# sender.net
KiCad netlist of a schematic drawn in Altium Designer
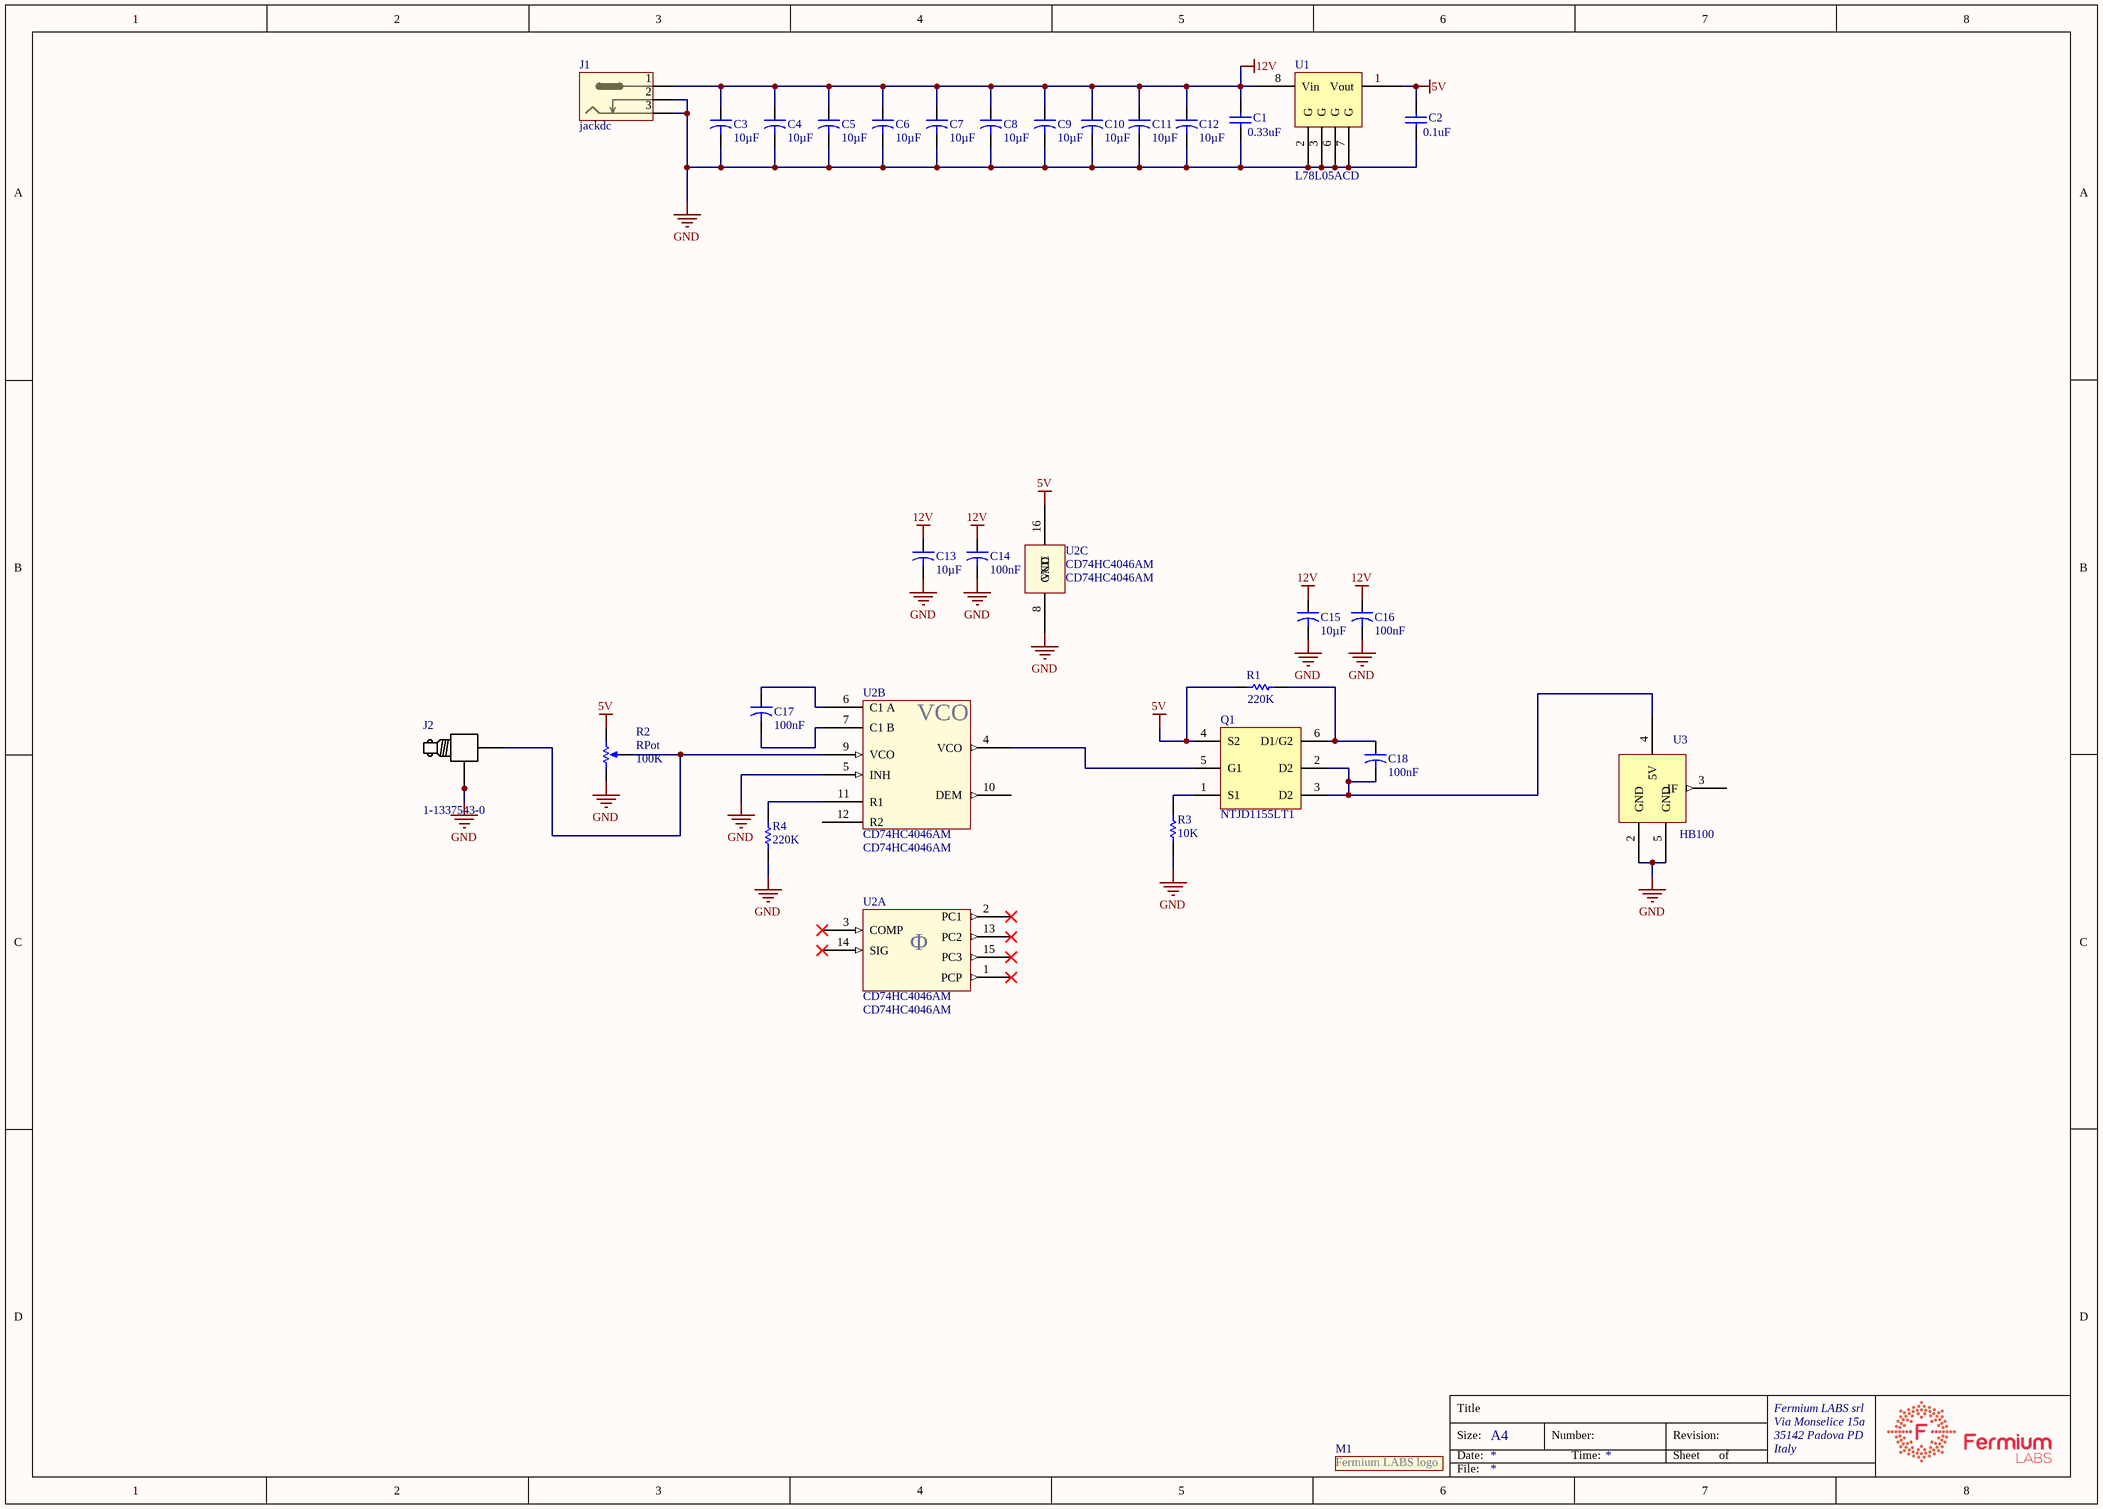
[diagram p0: sender.SchDoc]

(export (version "E")
  (design (tool "Eeschema 10.0.6"))
  (components
    (comp (ref "C1")
      (value "0.33uF")
      (footprint "RAD-0.3")
      (description "Capacitor")
      (fields (field (name "PUBLISHER") "Altium Limited"))
      (libsource (lib "Miscellaneous Devices") (part "Cap"))
    )
    (comp (ref "C2")
      (value "0.1uF")
      (footprint "RAD-0.3")
      (description "Capacitor")
      (fields (field (name "PUBLISHER") "Altium Limited"))
      (libsource (lib "Miscellaneous Devices") (part "Cap"))
    )
    (comp (ref "C3")
      (value "~")
      (footprint "Passives:CAP 1206/3216")
      (description "Capacitor")
      (fields
        (field (name "MANUFACTURER") "SAMSUNG")
        (field (name "MANUFACTURER PART NUMBER") "CL31A106KAHNNNE")
        (field (name "CAPACITANCE") "10µF")
        (field (name "PUBLISHER") "Altium Limited")
      )
      (libsource (lib "Miscellaneous Devices") (part "Cap2"))
    )
    (comp (ref "C4")
      (value "~")
      (footprint "Passives:CAP 1206/3216")
      (description "Capacitor")
      (fields
        (field (name "MANUFACTURER") "SAMSUNG")
        (field (name "MANUFACTURER PART NUMBER") "CL31A106KAHNNNE")
        (field (name "CAPACITANCE") "10µF")
        (field (name "PUBLISHER") "Altium Limited")
      )
      (libsource (lib "Miscellaneous Devices") (part "Cap2"))
    )
    (comp (ref "C5")
      (value "~")
      (footprint "Passives:CAP 1206/3216")
      (description "Capacitor")
      (fields
        (field (name "MANUFACTURER") "SAMSUNG")
        (field (name "MANUFACTURER PART NUMBER") "CL31A106KAHNNNE")
        (field (name "CAPACITANCE") "10µF")
        (field (name "PUBLISHER") "Altium Limited")
      )
      (libsource (lib "Miscellaneous Devices") (part "Cap2"))
    )
    (comp (ref "C6")
      (value "~")
      (footprint "Passives:CAP 1206/3216")
      (description "Capacitor")
      (fields
        (field (name "MANUFACTURER") "SAMSUNG")
        (field (name "MANUFACTURER PART NUMBER") "CL31A106KAHNNNE")
        (field (name "CAPACITANCE") "10µF")
        (field (name "PUBLISHER") "Altium Limited")
      )
      (libsource (lib "Miscellaneous Devices") (part "Cap2"))
    )
    (comp (ref "C7")
      (value "~")
      (footprint "Passives:CAP 1206/3216")
      (description "Capacitor")
      (fields
        (field (name "MANUFACTURER") "SAMSUNG")
        (field (name "MANUFACTURER PART NUMBER") "CL31A106KAHNNNE")
        (field (name "CAPACITANCE") "10µF")
        (field (name "PUBLISHER") "Altium Limited")
      )
      (libsource (lib "Miscellaneous Devices") (part "Cap2"))
    )
    (comp (ref "C8")
      (value "~")
      (footprint "Passives:CAP 1206/3216")
      (description "Capacitor")
      (fields
        (field (name "MANUFACTURER") "SAMSUNG")
        (field (name "MANUFACTURER PART NUMBER") "CL31A106KAHNNNE")
        (field (name "CAPACITANCE") "10µF")
        (field (name "PUBLISHER") "Altium Limited")
      )
      (libsource (lib "Miscellaneous Devices") (part "Cap2"))
    )
    (comp (ref "C9")
      (value "~")
      (footprint "Passives:CAP 1206/3216")
      (description "Capacitor")
      (fields
        (field (name "MANUFACTURER") "SAMSUNG")
        (field (name "MANUFACTURER PART NUMBER") "CL31A106KAHNNNE")
        (field (name "CAPACITANCE") "10µF")
        (field (name "PUBLISHER") "Altium Limited")
      )
      (libsource (lib "Miscellaneous Devices") (part "Cap2"))
    )
    (comp (ref "C10")
      (value "~")
      (footprint "Passives:CAP 1206/3216")
      (description "Capacitor")
      (fields
        (field (name "MANUFACTURER") "SAMSUNG")
        (field (name "MANUFACTURER PART NUMBER") "CL31A106KAHNNNE")
        (field (name "CAPACITANCE") "10µF")
        (field (name "PUBLISHER") "Altium Limited")
      )
      (libsource (lib "Miscellaneous Devices") (part "Cap2"))
    )
    (comp (ref "C11")
      (value "~")
      (footprint "Passives:CAP 1206/3216")
      (description "Capacitor")
      (fields
        (field (name "MANUFACTURER") "SAMSUNG")
        (field (name "MANUFACTURER PART NUMBER") "CL31A106KAHNNNE")
        (field (name "CAPACITANCE") "10µF")
        (field (name "PUBLISHER") "Altium Limited")
      )
      (libsource (lib "Miscellaneous Devices") (part "Cap2"))
    )
    (comp (ref "C12")
      (value "~")
      (footprint "Passives:CAP 1206/3216")
      (description "Capacitor")
      (fields
        (field (name "MANUFACTURER") "SAMSUNG")
        (field (name "MANUFACTURER PART NUMBER") "CL31A106KAHNNNE")
        (field (name "CAPACITANCE") "10µF")
        (field (name "PUBLISHER") "Altium Limited")
      )
      (libsource (lib "Miscellaneous Devices") (part "Cap2"))
    )
    (comp (ref "C13")
      (value "~")
      (footprint "Passives:CAP 1206/3216")
      (description "Capacitor")
      (fields
        (field (name "MANUFACTURER") "SAMSUNG")
        (field (name "MANUFACTURER PART NUMBER") "CL31A106KAHNNNE")
        (field (name "CAPACITANCE") "10µF")
        (field (name "PUBLISHER") "Altium Limited")
      )
      (libsource (lib "Miscellaneous Devices") (part "Cap2"))
    )
    (comp (ref "C14")
      (value "~")
      (footprint "Passives:CAP 0805/2012")
      (description "Capacitor")
      (fields
        (field (name "CAPACITANCE") "100nF")
        (field (name "MANUFACTURER") "YAGEO")
        (field (name "MANUFACTURER PART NUMBER") "CC0805JRX7R9BB104")
      )
      (libsource (lib "Miscellaneous Devices") (part "Cap2"))
    )
    (comp (ref "C15")
      (value "~")
      (footprint "Passives:CAP 1206/3216")
      (description "Capacitor")
      (fields
        (field (name "MANUFACTURER") "SAMSUNG")
        (field (name "MANUFACTURER PART NUMBER") "CL31A106KAHNNNE")
        (field (name "CAPACITANCE") "10µF")
        (field (name "PUBLISHER") "Altium Limited")
      )
      (libsource (lib "Miscellaneous Devices") (part "Cap2"))
    )
    (comp (ref "C16")
      (value "~")
      (footprint "Passives:CAP 0805/2012")
      (description "Capacitor")
      (fields
        (field (name "CAPACITANCE") "100nF")
        (field (name "MANUFACTURER") "YAGEO")
        (field (name "MANUFACTURER PART NUMBER") "CC0805JRX7R9BB104")
      )
      (libsource (lib "Miscellaneous Devices") (part "Cap2"))
    )
    (comp (ref "C17")
      (value "~")
      (footprint "Passives:CAP 0805/2012")
      (description "Capacitor")
      (fields
        (field (name "CAPACITANCE") "100nF")
        (field (name "MANUFACTURER") "YAGEO")
        (field (name "MANUFACTURER PART NUMBER") "CC0805JRX7R9BB104")
      )
      (libsource (lib "Miscellaneous Devices") (part "Cap2"))
    )
    (comp (ref "C18")
      (value "~")
      (footprint "Passives:CAP 0805/2012")
      (description "Capacitor")
      (fields
        (field (name "CAPACITANCE") "100nF")
        (field (name "MANUFACTURER") "YAGEO")
        (field (name "MANUFACTURER PART NUMBER") "CC0805JRX7R9BB104")
      )
      (libsource (lib "Miscellaneous Devices") (part "Cap2"))
    )
    (comp (ref "J1")
      (value "jackdc")
      (footprint "custom_components:dc-jack")
      (libsource (lib "custom_components") (part "jackdc"))
    )
    (comp (ref "J2")
      (value "~")
      (footprint "BNC-RA")
      (description "connector bnc")
      (fields
        (field (name "SUPPLIER PART NUMBER 1") "1-1337543-0")
        (field (name "MANUFACTURER") "TE CONNECTIVITY")
        (field (name "MANUFACTURER PART NUMBER") "1-1337543-0")
      )
      (libsource (lib "TH Connectors") (part "BNC-PCB-RA"))
    )
    (comp (ref "M1")
      (value "fermiumlabs-logo")
      (footprint "frm-small")
      (libsource (lib "custom_components") (part "fermiumlabs-logo"))
    )
    (comp (ref "Q1")
      (value "NTJD1155LT1")
      (footprint "ONSC-SC70-6-419B-02_W_V")
      (fields (field (name "MANUFACTURER") "On Semiconductor"))
      (libsource (lib "ON Semi MOSFETs") (part "NTJD1155LT1"))
    )
    (comp (ref "R1")
      (value "220K")
      (footprint "RES 0805/2012")
      (description "Resistor")
      (fields
        (field (name "MANUFACTURER") "Royal Electronic Factory")
        (field (name "MANUFACTURER PART NUMBER") "0805S8J0224T5E")
      )
      (libsource (lib "Miscellaneous Devices") (part "Res1"))
    )
    (comp (ref "R2")
      (value "RPot")
      (footprint "VR5")
      (description "Potentiometer")
      (fields (field (name "ALTIUM_VALUE") "100K"))
      (libsource (lib "Miscellaneous Devices") (part "RPot"))
    )
    (comp (ref "R3")
      (value "10K")
      (footprint "AXIAL-0.3")
      (description "Resistor")
      (fields (field (name "Comment") "Res1") (field (name "PUBLISHER") "Altium Limited"))
      (libsource (lib "Miscellaneous Devices") (part "Res1"))
    )
    (comp (ref "R4")
      (value "220K")
      (footprint "RES 0805/2012")
      (description "Resistor")
      (fields
        (field (name "MANUFACTURER") "Royal Electronic Factory")
        (field (name "MANUFACTURER PART NUMBER") "0805S8J0224T5E")
      )
      (libsource (lib "Miscellaneous Devices") (part "Res1"))
    )
    (comp (ref "U1")
      (value "L78L05ACD")
      (footprint "ST SOIC-8N")
      (fields (field (name "SUPPLIER PART NUMBER 1") "L78L05ACD"))
      (libsource (lib "custom_components_ltk_mw") (part "L78L05ACD"))
    )
    (comp (ref "U2")
      (value "CD74HC4046AM")
      (footprint "SO16")
      (fields (field (name "SUPPLIER PART NUMBER 1") "CD74HC4046AM"))
      (libsource (lib "custom_components_ltk_mw") (part "CD74HC4046AM"))
    )
    (comp (ref "U3")
      (value "HB100")
      (footprint "HB100")
      (fields
        (field (name "MANUFACTURER") "China unspecified")
        (field (name "SUPPLIER PART NUMBER 1") "HB100")
      )
      (libsource (lib "custom_components_ltk_mw") (part "HB100"))
    )
  )
  (nets
    (net (code "1") (name "5V") (class "Default")
      (node (ref "C2") (pin "2") (pinfunction "2_2") (pintype "passive"))
      (node (ref "Q1") (pin "4") (pinfunction "S2_4") (pintype "passive"))
      (node (ref "R1") (pin "1") (pinfunction "1_1") (pintype "passive"))
      (node (ref "R2") (pin "2") (pinfunction "BOT_2") (pintype "passive"))
      (node (ref "U1") (pin "1") (pinfunction "Vout_1") (pintype "power_in"))
      (node (ref "U2") (pin "16") (pinfunction "VCC_16") (pintype "power_in"))
    )
    (net (code "2") (name "12V") (class "Default")
      (node (ref "C1") (pin "2") (pinfunction "2_2") (pintype "passive"))
      (node (ref "C10") (pin "1") (pinfunction "1_1") (pintype "passive"))
      (node (ref "C11") (pin "1") (pinfunction "1_1") (pintype "passive"))
      (node (ref "C12") (pin "1") (pinfunction "1_1") (pintype "passive"))
      (node (ref "C13") (pin "1") (pinfunction "1_1") (pintype "passive"))
      (node (ref "C14") (pin "1") (pinfunction "1_1") (pintype "passive"))
      (node (ref "C15") (pin "1") (pinfunction "1_1") (pintype "passive"))
      (node (ref "C16") (pin "1") (pinfunction "1_1") (pintype "passive"))
      (node (ref "C3") (pin "1") (pinfunction "1_1") (pintype "passive"))
      (node (ref "C4") (pin "1") (pinfunction "1_1") (pintype "passive"))
      (node (ref "C5") (pin "1") (pinfunction "1_1") (pintype "passive"))
      (node (ref "C6") (pin "1") (pinfunction "1_1") (pintype "passive"))
      (node (ref "C7") (pin "1") (pinfunction "1_1") (pintype "passive"))
      (node (ref "C8") (pin "1") (pinfunction "1_1") (pintype "passive"))
      (node (ref "C9") (pin "1") (pinfunction "1_1") (pintype "passive"))
      (node (ref "J1") (pin "1") (pinfunction "1_1") (pintype "passive"))
      (node (ref "U1") (pin "8") (pinfunction "Vin_8") (pintype "power_in"))
    )
    (net (code "3") (name "GND") (class "Default")
      (node (ref "C1") (pin "1") (pinfunction "1_1") (pintype "passive"))
      (node (ref "C10") (pin "2") (pinfunction "2_2") (pintype "passive"))
      (node (ref "C11") (pin "2") (pinfunction "2_2") (pintype "passive"))
      (node (ref "C12") (pin "2") (pinfunction "2_2") (pintype "passive"))
      (node (ref "C13") (pin "2") (pinfunction "2_2") (pintype "passive"))
      (node (ref "C14") (pin "2") (pinfunction "2_2") (pintype "passive"))
      (node (ref "C15") (pin "2") (pinfunction "2_2") (pintype "passive"))
      (node (ref "C16") (pin "2") (pinfunction "2_2") (pintype "passive"))
      (node (ref "C2") (pin "1") (pinfunction "1_1") (pintype "passive"))
      (node (ref "C3") (pin "2") (pinfunction "2_2") (pintype "passive"))
      (node (ref "C4") (pin "2") (pinfunction "2_2") (pintype "passive"))
      (node (ref "C5") (pin "2") (pinfunction "2_2") (pintype "passive"))
      (node (ref "C6") (pin "2") (pinfunction "2_2") (pintype "passive"))
      (node (ref "C7") (pin "2") (pinfunction "2_2") (pintype "passive"))
      (node (ref "C8") (pin "2") (pinfunction "2_2") (pintype "passive"))
      (node (ref "C9") (pin "2") (pinfunction "2_2") (pintype "passive"))
      (node (ref "J1") (pin "2") (pinfunction "2_2") (pintype "passive"))
      (node (ref "J1") (pin "3") (pinfunction "3_3") (pintype "passive"))
      (node (ref "J2") (pin "2") (pinfunction "gnd_2") (pintype "passive"))
      (node (ref "J2") (pin "A") (pinfunction "A_A") (pintype "passive"))
      (node (ref "J2") (pin "B") (pinfunction "B_B") (pintype "passive"))
      (node (ref "R2") (pin "1") (pinfunction "TOP_1") (pintype "passive"))
      (node (ref "R3") (pin "2") (pinfunction "2_2") (pintype "passive"))
      (node (ref "R4") (pin "1") (pinfunction "1_1") (pintype "passive"))
      (node (ref "U1") (pin "2") (pinfunction "G_2") (pintype "power_in"))
      (node (ref "U1") (pin "3") (pinfunction "G_3") (pintype "power_in"))
      (node (ref "U1") (pin "6") (pinfunction "G_6") (pintype "power_in"))
      (node (ref "U1") (pin "7") (pinfunction "G_7") (pintype "power_in"))
      (node (ref "U2") (pin "5") (pinfunction "INH_5") (pintype "input"))
      (node (ref "U2") (pin "8") (pinfunction "GND_8") (pintype "power_in"))
      (node (ref "U3") (pin "2") (pinfunction "GND_2") (pintype "power_in"))
      (node (ref "U3") (pin "5") (pinfunction "GND_5") (pintype "power_in"))
    )
    (net (code "4") (name "Net-(Q1-D1{slash}G2)") (class "Default")
      (node (ref "C18") (pin "1") (pinfunction "1_1") (pintype "passive"))
      (node (ref "Q1") (pin "6") (pinfunction "D1/G2_6") (pintype "passive"))
      (node (ref "R1") (pin "2") (pinfunction "2_2") (pintype "passive"))
    )
    (net (code "5") (name "Net-(Q1-G1)") (class "Default")
      (node (ref "Q1") (pin "5") (pinfunction "G1_5") (pintype "passive"))
      (node (ref "U2") (pin "4") (pinfunction "VCO_4") (pintype "output"))
    )
    (net (code "6") (name "Net-(Q1-S1)") (class "Default")
      (node (ref "Q1") (pin "1") (pinfunction "S1_1") (pintype "passive"))
      (node (ref "R3") (pin "1") (pinfunction "1_1") (pintype "passive"))
    )
    (net (code "7") (name "Net-(R2-TAP)") (class "Default")
      (node (ref "J2") (pin "1") (pinfunction "1_1") (pintype "passive"))
      (node (ref "R2") (pin "3") (pinfunction "TAP_3") (pintype "passive"))
      (node (ref "U2") (pin "9") (pinfunction "VCO_9") (pintype "input"))
    )
    (net (code "8") (name "Net-(U2B-C1_A)") (class "Default")
      (node (ref "C17") (pin "1") (pinfunction "1_1") (pintype "passive"))
      (node (ref "U2") (pin "6") (pinfunction "C1_A_6") (pintype "passive"))
    )
    (net (code "9") (name "Net-(U2B-C1_B)") (class "Default")
      (node (ref "C17") (pin "2") (pinfunction "2_2") (pintype "passive"))
      (node (ref "U2") (pin "7") (pinfunction "C1_B_7") (pintype "passive"))
    )
    (net (code "10") (name "Net-(U2B-R1)") (class "Default")
      (node (ref "R4") (pin "2") (pinfunction "2_2") (pintype "passive"))
      (node (ref "U2") (pin "11") (pinfunction "R1_11") (pintype "passive"))
    )
    (net (code "11") (name "Net-(U3-5V)") (class "Default")
      (node (ref "C18") (pin "2") (pinfunction "2_2") (pintype "passive"))
      (node (ref "Q1") (pin "2") (pinfunction "D2_2") (pintype "passive"))
      (node (ref "Q1") (pin "3") (pinfunction "D2_3") (pintype "passive"))
      (node (ref "U3") (pin "4") (pinfunction "5V_4") (pintype "power_in"))
    )
    (net (code "12") (name "unconnected-(U2A-COMP-Pad3)") (class "Default")
      (node (ref "U2") (pin "3") (pinfunction "COMP_3") (pintype "input+no_connect"))
    )
    (net (code "13") (name "unconnected-(U2A-PC1-Pad2)") (class "Default")
      (node (ref "U2") (pin "2") (pinfunction "PC1_2") (pintype "output+no_connect"))
    )
    (net (code "14") (name "unconnected-(U2A-PC2-Pad13)") (class "Default")
      (node (ref "U2") (pin "13") (pinfunction "PC2_13") (pintype "output+no_connect"))
    )
    (net (code "15") (name "unconnected-(U2A-PC3-Pad15)") (class "Default")
      (node (ref "U2") (pin "15") (pinfunction "PC3_15") (pintype "output+no_connect"))
    )
    (net (code "16") (name "unconnected-(U2A-PCP-Pad1)") (class "Default")
      (node (ref "U2") (pin "1") (pinfunction "PCP_1") (pintype "output+no_connect"))
    )
    (net (code "17") (name "unconnected-(U2A-SIG-Pad14)") (class "Default")
      (node (ref "U2") (pin "14") (pinfunction "SIG_14") (pintype "input+no_connect"))
    )
    (net (code "18") (name "unconnected-(U2B-DEM-Pad10)") (class "Default")
      (node (ref "U2") (pin "10") (pinfunction "DEM_10") (pintype "output"))
    )
    (net (code "19") (name "unconnected-(U2B-R2-Pad12)") (class "Default")
      (node (ref "U2") (pin "12") (pinfunction "R2_12") (pintype "passive"))
    )
    (net (code "20") (name "unconnected-(U3-IF-Pad3)") (class "Default")
      (node (ref "U3") (pin "3") (pinfunction "IF_3") (pintype "output"))
    )
  )
)
